# Voltage_Regulators.net
KiCad netlist of a schematic drawn in Altium Designer
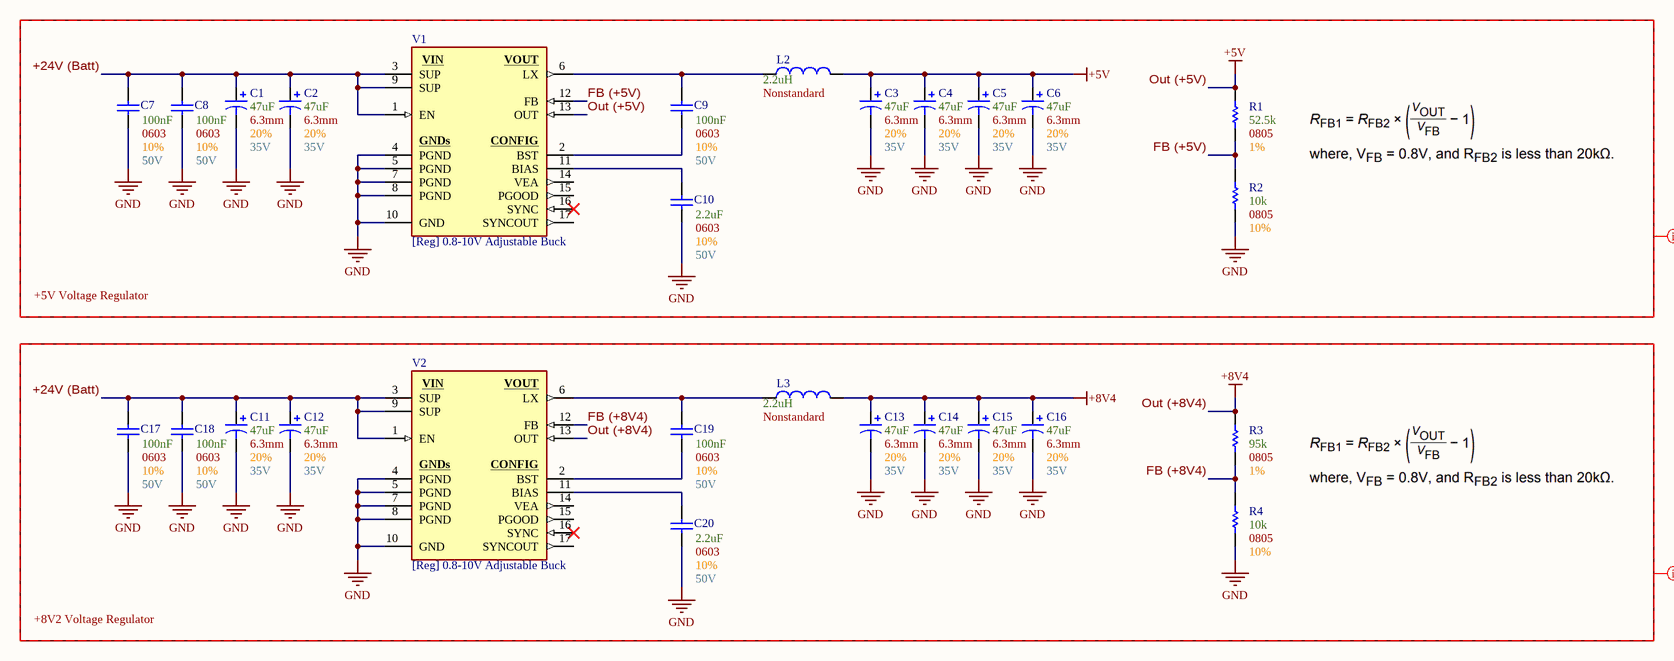
[diagram p0: Voltage Regulators.SchDoc]

(export (version "E")
  (design (tool "Eeschema 10.0.6"))
  (components
    (comp (ref "C1")
      (value "SMD Polarized")
      (footprint "[Cap] SMD Polarized, 6.3mm")
      (fields
        (field (name "TOLERANCE") "20%")
        (field (name "MAX VOLTAGE") "35V")
        (field (name "CAPACITANCE") "47uF")
        (field (name "DIAMETER") "6.3mm")
      )
      (libsource (lib "RADM Components") (part "[Cap] SMD Polarized"))
    )
    (comp (ref "C2")
      (value "SMD Polarized")
      (footprint "[Cap] SMD Polarized, 6.3mm")
      (fields
        (field (name "TOLERANCE") "20%")
        (field (name "MAX VOLTAGE") "35V")
        (field (name "CAPACITANCE") "47uF")
        (field (name "DIAMETER") "6.3mm")
      )
      (libsource (lib "RADM Components") (part "[Cap] SMD Polarized"))
    )
    (comp (ref "C3")
      (value "SMD Polarized")
      (footprint "[Cap] SMD Polarized, 6.3mm")
      (fields
        (field (name "TOLERANCE") "20%")
        (field (name "MAX VOLTAGE") "35V")
        (field (name "CAPACITANCE") "47uF")
        (field (name "DIAMETER") "6.3mm")
      )
      (libsource (lib "RADM Components") (part "[Cap] SMD Polarized"))
    )
    (comp (ref "C4")
      (value "SMD Polarized")
      (footprint "[Cap] SMD Polarized, 6.3mm")
      (fields
        (field (name "TOLERANCE") "20%")
        (field (name "MAX VOLTAGE") "35V")
        (field (name "CAPACITANCE") "47uF")
        (field (name "DIAMETER") "6.3mm")
      )
      (libsource (lib "RADM Components") (part "[Cap] SMD Polarized"))
    )
    (comp (ref "C5")
      (value "SMD Polarized")
      (footprint "[Cap] SMD Polarized, 6.3mm")
      (fields
        (field (name "TOLERANCE") "20%")
        (field (name "MAX VOLTAGE") "35V")
        (field (name "CAPACITANCE") "47uF")
        (field (name "DIAMETER") "6.3mm")
      )
      (libsource (lib "RADM Components") (part "[Cap] SMD Polarized"))
    )
    (comp (ref "C6")
      (value "SMD Polarized")
      (footprint "[Cap] SMD Polarized, 6.3mm")
      (fields
        (field (name "TOLERANCE") "20%")
        (field (name "MAX VOLTAGE") "35V")
        (field (name "CAPACITANCE") "47uF")
        (field (name "DIAMETER") "6.3mm")
      )
      (libsource (lib "RADM Components") (part "[Cap] SMD Polarized"))
    )
    (comp (ref "C7")
      (value "SMD Nonpolarized")
      (footprint "[Cap] SMD 0603")
      (fields
        (field (name "VOLTAGE") "50V")
        (field (name "TOLERANCE") "10%")
        (field (name "SIZE PACKAGE") "0603")
        (field (name "CAPACITANCE") "100nF")
      )
      (libsource (lib "RADM Components") (part "[Cap] SMD Nonpolarized"))
    )
    (comp (ref "C8")
      (value "SMD Nonpolarized")
      (footprint "[Cap] SMD 0603")
      (fields
        (field (name "VOLTAGE") "50V")
        (field (name "TOLERANCE") "10%")
        (field (name "SIZE PACKAGE") "0603")
        (field (name "CAPACITANCE") "100nF")
      )
      (libsource (lib "RADM Components") (part "[Cap] SMD Nonpolarized"))
    )
    (comp (ref "C9")
      (value "SMD Nonpolarized")
      (footprint "[Cap] SMD 0603")
      (fields
        (field (name "VOLTAGE") "50V")
        (field (name "TOLERANCE") "10%")
        (field (name "SIZE PACKAGE") "0603")
        (field (name "CAPACITANCE") "100nF")
      )
      (libsource (lib "RADM Components") (part "[Cap] SMD Nonpolarized"))
    )
    (comp (ref "C10")
      (value "SMD Nonpolarized")
      (footprint "[Cap] SMD 0603")
      (fields
        (field (name "VOLTAGE") "50V")
        (field (name "TOLERANCE") "10%")
        (field (name "SIZE PACKAGE") "0603")
        (field (name "CAPACITANCE") "2.2uF")
      )
      (libsource (lib "RADM Components") (part "[Cap] SMD Nonpolarized"))
    )
    (comp (ref "C11")
      (value "SMD Polarized")
      (footprint "[Cap] SMD Polarized, 6.3mm")
      (fields
        (field (name "TOLERANCE") "20%")
        (field (name "MAX VOLTAGE") "35V")
        (field (name "CAPACITANCE") "47uF")
        (field (name "DIAMETER") "6.3mm")
      )
      (libsource (lib "RADM Components") (part "[Cap] SMD Polarized"))
    )
    (comp (ref "C12")
      (value "SMD Polarized")
      (footprint "[Cap] SMD Polarized, 6.3mm")
      (fields
        (field (name "TOLERANCE") "20%")
        (field (name "MAX VOLTAGE") "35V")
        (field (name "CAPACITANCE") "47uF")
        (field (name "DIAMETER") "6.3mm")
      )
      (libsource (lib "RADM Components") (part "[Cap] SMD Polarized"))
    )
    (comp (ref "C13")
      (value "SMD Polarized")
      (footprint "[Cap] SMD Polarized, 6.3mm")
      (fields
        (field (name "TOLERANCE") "20%")
        (field (name "MAX VOLTAGE") "35V")
        (field (name "CAPACITANCE") "47uF")
        (field (name "DIAMETER") "6.3mm")
      )
      (libsource (lib "RADM Components") (part "[Cap] SMD Polarized"))
    )
    (comp (ref "C14")
      (value "SMD Polarized")
      (footprint "[Cap] SMD Polarized, 6.3mm")
      (fields
        (field (name "TOLERANCE") "20%")
        (field (name "MAX VOLTAGE") "35V")
        (field (name "CAPACITANCE") "47uF")
        (field (name "DIAMETER") "6.3mm")
      )
      (libsource (lib "RADM Components") (part "[Cap] SMD Polarized"))
    )
    (comp (ref "C15")
      (value "SMD Polarized")
      (footprint "[Cap] SMD Polarized, 6.3mm")
      (fields
        (field (name "TOLERANCE") "20%")
        (field (name "MAX VOLTAGE") "35V")
        (field (name "CAPACITANCE") "47uF")
        (field (name "DIAMETER") "6.3mm")
      )
      (libsource (lib "RADM Components") (part "[Cap] SMD Polarized"))
    )
    (comp (ref "C16")
      (value "SMD Polarized")
      (footprint "[Cap] SMD Polarized, 6.3mm")
      (fields
        (field (name "TOLERANCE") "20%")
        (field (name "MAX VOLTAGE") "35V")
        (field (name "CAPACITANCE") "47uF")
        (field (name "DIAMETER") "6.3mm")
      )
      (libsource (lib "RADM Components") (part "[Cap] SMD Polarized"))
    )
    (comp (ref "C17")
      (value "SMD Nonpolarized")
      (footprint "[Cap] SMD 0603")
      (fields
        (field (name "VOLTAGE") "50V")
        (field (name "TOLERANCE") "10%")
        (field (name "SIZE PACKAGE") "0603")
        (field (name "CAPACITANCE") "100nF")
      )
      (libsource (lib "RADM Components") (part "[Cap] SMD Nonpolarized"))
    )
    (comp (ref "C18")
      (value "SMD Nonpolarized")
      (footprint "[Cap] SMD 0603")
      (fields
        (field (name "VOLTAGE") "50V")
        (field (name "TOLERANCE") "10%")
        (field (name "SIZE PACKAGE") "0603")
        (field (name "CAPACITANCE") "100nF")
      )
      (libsource (lib "RADM Components") (part "[Cap] SMD Nonpolarized"))
    )
    (comp (ref "C19")
      (value "SMD Nonpolarized")
      (footprint "[Cap] SMD 0603")
      (fields
        (field (name "VOLTAGE") "50V")
        (field (name "TOLERANCE") "10%")
        (field (name "SIZE PACKAGE") "0603")
        (field (name "CAPACITANCE") "100nF")
      )
      (libsource (lib "RADM Components") (part "[Cap] SMD Nonpolarized"))
    )
    (comp (ref "C20")
      (value "SMD Nonpolarized")
      (footprint "[Cap] SMD 0603")
      (fields
        (field (name "VOLTAGE") "50V")
        (field (name "TOLERANCE") "10%")
        (field (name "SIZE PACKAGE") "0603")
        (field (name "CAPACITANCE") "2.2uF")
      )
      (libsource (lib "RADM Components") (part "[Cap] SMD Nonpolarized"))
    )
    (comp (ref "L2")
      (value "SMD Inductor")
      (footprint "[Inductor] 7.4 X 6.6 X 3 MM")
      (fields (field (name "SIZE PACKAGE") "Nonstandard") (field (name "INDUCTANCE") "2.2uH"))
      (libsource (lib "RADM Components") (part "[Inductor] SMD Inductor"))
    )
    (comp (ref "L3")
      (value "SMD Inductor")
      (footprint "[Inductor] 7.4 X 6.6 X 3 MM")
      (fields (field (name "SIZE PACKAGE") "Nonstandard") (field (name "INDUCTANCE") "2.2uH"))
      (libsource (lib "RADM Components") (part "[Inductor] SMD Inductor"))
    )
    (comp (ref "R1")
      (value "[Res] SMD Resistor")
      (footprint "[Res] SMD 0805")
      (description "Generic")
      (fields
        (field (name "TOLERANCE") "1%")
        (field (name "RESISTANCE") "52.5k")
        (field (name "SIZE PACKAGE") "0805")
      )
      (libsource (lib "RADM Components") (part "[Res] SMD Resistor"))
    )
    (comp (ref "R2")
      (value "[Res] SMD Resistor")
      (footprint "[Res] SMD 0805")
      (description "Generic")
      (fields
        (field (name "TOLERANCE") "10%")
        (field (name "RESISTANCE") "10k")
        (field (name "SIZE PACKAGE") "0805")
      )
      (libsource (lib "RADM Components") (part "[Res] SMD Resistor"))
    )
    (comp (ref "R3")
      (value "[Res] SMD Resistor")
      (footprint "[Res] SMD 0805")
      (description "Generic")
      (fields
        (field (name "TOLERANCE") "1%")
        (field (name "RESISTANCE") "95k")
        (field (name "SIZE PACKAGE") "0805")
      )
      (libsource (lib "RADM Components") (part "[Res] SMD Resistor"))
    )
    (comp (ref "R4")
      (value "[Res] SMD Resistor")
      (footprint "[Res] SMD 0805")
      (description "Generic")
      (fields
        (field (name "TOLERANCE") "10%")
        (field (name "RESISTANCE") "10k")
        (field (name "SIZE PACKAGE") "0805")
      )
      (libsource (lib "RADM Components") (part "[Res] SMD Resistor"))
    )
    (comp (ref "V1")
      (value "[Reg] 0.8-10V Adjustable Buck")
      (footprint "[Reg] 0.8-10V Adjustable Buck")
      (description "MAX20408AFOF/VY+")
      (libsource (lib "RADM Components") (part "[Reg] 0.8-10V Adjustable Buck"))
    )
    (comp (ref "V2")
      (value "[Reg] 0.8-10V Adjustable Buck")
      (footprint "[Reg] 0.8-10V Adjustable Buck")
      (description "MAX20408AFOF/VY+")
      (libsource (lib "RADM Components") (part "[Reg] 0.8-10V Adjustable Buck"))
    )
  )
  (nets
    (net (code "1") (name "+5V") (class "Default")
      (node (ref "C3") (pin "1") (pinfunction "1_1") (pintype "passive"))
      (node (ref "C4") (pin "1") (pinfunction "1_1") (pintype "passive"))
      (node (ref "C5") (pin "1") (pinfunction "1_1") (pintype "passive"))
      (node (ref "C6") (pin "1") (pinfunction "1_1") (pintype "passive"))
      (node (ref "L2") (pin "2") (pinfunction "2_2") (pintype "passive"))
      (node (ref "R1") (pin "2") (pinfunction "2_2") (pintype "passive"))
      (node (ref "V1") (pin "13") (pinfunction "OUT_13") (pintype "input"))
    )
    (net (code "2") (name "+8V4") (class "Default")
      (node (ref "C13") (pin "1") (pinfunction "1_1") (pintype "passive"))
      (node (ref "C14") (pin "1") (pinfunction "1_1") (pintype "passive"))
      (node (ref "C15") (pin "1") (pinfunction "1_1") (pintype "passive"))
      (node (ref "C16") (pin "1") (pinfunction "1_1") (pintype "passive"))
      (node (ref "L3") (pin "2") (pinfunction "2_2") (pintype "passive"))
      (node (ref "R3") (pin "2") (pinfunction "2_2") (pintype "passive"))
      (node (ref "V2") (pin "13") (pinfunction "OUT_13") (pintype "input"))
    )
    (net (code "3") (name "/+24V (Batt)") (class "Default")
      (node (ref "C1") (pin "1") (pinfunction "1_1") (pintype "passive"))
      (node (ref "C11") (pin "1") (pinfunction "1_1") (pintype "passive"))
      (node (ref "C12") (pin "1") (pinfunction "1_1") (pintype "passive"))
      (node (ref "C17") (pin "2") (pinfunction "2_2") (pintype "passive"))
      (node (ref "C18") (pin "2") (pinfunction "2_2") (pintype "passive"))
      (node (ref "C2") (pin "1") (pinfunction "1_1") (pintype "passive"))
      (node (ref "C7") (pin "2") (pinfunction "2_2") (pintype "passive"))
      (node (ref "C8") (pin "2") (pinfunction "2_2") (pintype "passive"))
      (node (ref "V1") (pin "1") (pinfunction "EN_1") (pintype "input"))
      (node (ref "V1") (pin "3") (pinfunction "SUP_3") (pintype "power_in"))
      (node (ref "V1") (pin "9") (pinfunction "SUP_9") (pintype "power_in"))
      (node (ref "V2") (pin "1") (pinfunction "EN_1") (pintype "input"))
      (node (ref "V2") (pin "3") (pinfunction "SUP_3") (pintype "power_in"))
      (node (ref "V2") (pin "9") (pinfunction "SUP_9") (pintype "power_in"))
    )
    (net (code "4") (name "/FB (+5V)") (class "Default")
      (node (ref "R1") (pin "1") (pinfunction "1_1") (pintype "passive"))
      (node (ref "R2") (pin "2") (pinfunction "2_2") (pintype "passive"))
      (node (ref "V1") (pin "12") (pinfunction "FB_12") (pintype "input"))
    )
    (net (code "5") (name "/FB (+8V4)") (class "Default")
      (node (ref "R3") (pin "1") (pinfunction "1_1") (pintype "passive"))
      (node (ref "R4") (pin "2") (pinfunction "2_2") (pintype "passive"))
      (node (ref "V2") (pin "12") (pinfunction "FB_12") (pintype "input"))
    )
    (net (code "6") (name "GND") (class "Default")
      (node (ref "C1") (pin "2") (pinfunction "2_2") (pintype "passive"))
      (node (ref "C10") (pin "1") (pinfunction "1_1") (pintype "passive"))
      (node (ref "C11") (pin "2") (pinfunction "2_2") (pintype "passive"))
      (node (ref "C12") (pin "2") (pinfunction "2_2") (pintype "passive"))
      (node (ref "C13") (pin "2") (pinfunction "2_2") (pintype "passive"))
      (node (ref "C14") (pin "2") (pinfunction "2_2") (pintype "passive"))
      (node (ref "C15") (pin "2") (pinfunction "2_2") (pintype "passive"))
      (node (ref "C16") (pin "2") (pinfunction "2_2") (pintype "passive"))
      (node (ref "C17") (pin "1") (pinfunction "1_1") (pintype "passive"))
      (node (ref "C18") (pin "1") (pinfunction "1_1") (pintype "passive"))
      (node (ref "C2") (pin "2") (pinfunction "2_2") (pintype "passive"))
      (node (ref "C20") (pin "1") (pinfunction "1_1") (pintype "passive"))
      (node (ref "C3") (pin "2") (pinfunction "2_2") (pintype "passive"))
      (node (ref "C4") (pin "2") (pinfunction "2_2") (pintype "passive"))
      (node (ref "C5") (pin "2") (pinfunction "2_2") (pintype "passive"))
      (node (ref "C6") (pin "2") (pinfunction "2_2") (pintype "passive"))
      (node (ref "C7") (pin "1") (pinfunction "1_1") (pintype "passive"))
      (node (ref "C8") (pin "1") (pinfunction "1_1") (pintype "passive"))
      (node (ref "R2") (pin "1") (pinfunction "1_1") (pintype "passive"))
      (node (ref "R4") (pin "1") (pinfunction "1_1") (pintype "passive"))
      (node (ref "V1") (pin "10") (pinfunction "GND_10") (pintype "power_in"))
      (node (ref "V1") (pin "4") (pinfunction "PGND_4") (pintype "power_in"))
      (node (ref "V1") (pin "5") (pinfunction "PGND_5") (pintype "power_in"))
      (node (ref "V1") (pin "7") (pinfunction "PGND_7") (pintype "power_in"))
      (node (ref "V1") (pin "8") (pinfunction "PGND_8") (pintype "power_in"))
      (node (ref "V2") (pin "10") (pinfunction "GND_10") (pintype "power_in"))
      (node (ref "V2") (pin "4") (pinfunction "PGND_4") (pintype "power_in"))
      (node (ref "V2") (pin "5") (pinfunction "PGND_5") (pintype "power_in"))
      (node (ref "V2") (pin "7") (pinfunction "PGND_7") (pintype "power_in"))
      (node (ref "V2") (pin "8") (pinfunction "PGND_8") (pintype "power_in"))
    )
    (net (code "7") (name "Net-(V1-BIAS)") (class "Default")
      (node (ref "C10") (pin "2") (pinfunction "2_2") (pintype "passive"))
      (node (ref "V1") (pin "11") (pinfunction "BIAS_11") (pintype "power_in"))
    )
    (net (code "8") (name "Net-(V1-BST)") (class "Default")
      (node (ref "C9") (pin "1") (pinfunction "1_1") (pintype "passive"))
      (node (ref "V1") (pin "2") (pinfunction "BST_2") (pintype "power_in"))
    )
    (net (code "9") (name "Net-(V1-LX)") (class "Default")
      (node (ref "C9") (pin "2") (pinfunction "2_2") (pintype "passive"))
      (node (ref "L2") (pin "1") (pinfunction "1_1") (pintype "passive"))
      (node (ref "V1") (pin "6") (pinfunction "LX_6") (pintype "output"))
    )
    (net (code "10") (name "Net-(V2-BIAS)") (class "Default")
      (node (ref "C20") (pin "2") (pinfunction "2_2") (pintype "passive"))
      (node (ref "V2") (pin "11") (pinfunction "BIAS_11") (pintype "power_in"))
    )
    (net (code "11") (name "Net-(V2-BST)") (class "Default")
      (node (ref "C19") (pin "1") (pinfunction "1_1") (pintype "passive"))
      (node (ref "V2") (pin "2") (pinfunction "BST_2") (pintype "power_in"))
    )
    (net (code "12") (name "Net-(V2-LX)") (class "Default")
      (node (ref "C19") (pin "2") (pinfunction "2_2") (pintype "passive"))
      (node (ref "L3") (pin "1") (pinfunction "1_1") (pintype "passive"))
      (node (ref "V2") (pin "6") (pinfunction "LX_6") (pintype "output"))
    )
    (net (code "13") (name "unconnected-(V1-PGOOD-Pad15)") (class "Default")
      (node (ref "V1") (pin "15") (pinfunction "PGOOD_15") (pintype "output"))
    )
    (net (code "14") (name "unconnected-(V1-SYNC-Pad16)") (class "Default")
      (node (ref "V1") (pin "16") (pinfunction "SYNC_16") (pintype "input+no_connect"))
    )
    (net (code "15") (name "unconnected-(V1-SYNCOUT-Pad17)") (class "Default")
      (node (ref "V1") (pin "17") (pinfunction "SYNCOUT_17") (pintype "output"))
    )
    (net (code "16") (name "unconnected-(V1-VEA-Pad14)") (class "Default")
      (node (ref "V1") (pin "14") (pinfunction "VEA_14") (pintype "output"))
    )
    (net (code "17") (name "unconnected-(V2-PGOOD-Pad15)") (class "Default")
      (node (ref "V2") (pin "15") (pinfunction "PGOOD_15") (pintype "output"))
    )
    (net (code "18") (name "unconnected-(V2-SYNC-Pad16)") (class "Default")
      (node (ref "V2") (pin "16") (pinfunction "SYNC_16") (pintype "input+no_connect"))
    )
    (net (code "19") (name "unconnected-(V2-SYNCOUT-Pad17)") (class "Default")
      (node (ref "V2") (pin "17") (pinfunction "SYNCOUT_17") (pintype "output"))
    )
    (net (code "20") (name "unconnected-(V2-VEA-Pad14)") (class "Default")
      (node (ref "V2") (pin "14") (pinfunction "VEA_14") (pintype "output"))
    )
  )
)
